# Schematic.net
KiCad netlist of a schematic drawn in Altium Designer
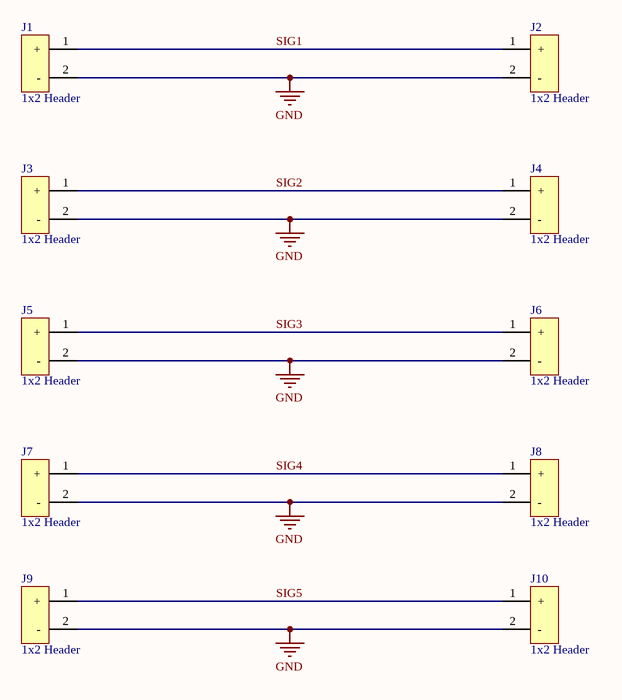
[diagram p0: Schematic.SchDoc]

(export (version "E")
  (design (tool "Eeschema 10.0.6"))
  (components
    (comp (ref "J1")
      (value "1x2 Header")
      (footprint "HDR1X2")
      (description "Headers & Wire Housings 2 PIN F/LK HEADER")
      (fields (field (name "MANUFACTURER") "Molex") (field (name "MANUFACTURER PART NUMBER") "22-29-2021"))
      (libsource (lib "") (part "22-29-2021_1"))
    )
    (comp (ref "J2")
      (value "1x2 Header")
      (footprint "HDR1X2")
      (description "Headers & Wire Housings 2 PIN F/LK HEADER")
      (fields (field (name "MANUFACTURER") "Molex") (field (name "MANUFACTURER PART NUMBER") "22-29-2021"))
      (libsource (lib "Schlib") (part "22-29-2021"))
    )
    (comp (ref "J3")
      (value "1x2 Header")
      (footprint "HDR1X2")
      (description "Headers & Wire Housings 2 PIN F/LK HEADER")
      (fields (field (name "MANUFACTURER") "Molex") (field (name "MANUFACTURER PART NUMBER") "22-29-2021"))
      (libsource (lib "") (part "22-29-2021_1"))
    )
    (comp (ref "J4")
      (value "1x2 Header")
      (footprint "HDR1X2")
      (description "Headers & Wire Housings 2 PIN F/LK HEADER")
      (fields (field (name "MANUFACTURER") "Molex") (field (name "MANUFACTURER PART NUMBER") "22-29-2021"))
      (libsource (lib "Schlib") (part "22-29-2021"))
    )
    (comp (ref "J5")
      (value "1x2 Header")
      (footprint "HDR1X2")
      (description "Headers & Wire Housings 2 PIN F/LK HEADER")
      (fields (field (name "MANUFACTURER") "Molex") (field (name "MANUFACTURER PART NUMBER") "22-29-2021"))
      (libsource (lib "") (part "22-29-2021_1"))
    )
    (comp (ref "J6")
      (value "1x2 Header")
      (footprint "HDR1X2")
      (description "Headers & Wire Housings 2 PIN F/LK HEADER")
      (fields (field (name "MANUFACTURER") "Molex") (field (name "MANUFACTURER PART NUMBER") "22-29-2021"))
      (libsource (lib "Schlib") (part "22-29-2021"))
    )
    (comp (ref "J7")
      (value "1x2 Header")
      (footprint "HDR1X2")
      (description "Headers & Wire Housings 2 PIN F/LK HEADER")
      (fields (field (name "MANUFACTURER") "Molex") (field (name "MANUFACTURER PART NUMBER") "22-29-2021"))
      (libsource (lib "") (part "22-29-2021_1"))
    )
    (comp (ref "J8")
      (value "1x2 Header")
      (footprint "HDR1X2")
      (description "Headers & Wire Housings 2 PIN F/LK HEADER")
      (fields (field (name "MANUFACTURER") "Molex") (field (name "MANUFACTURER PART NUMBER") "22-29-2021"))
      (libsource (lib "Schlib") (part "22-29-2021"))
    )
    (comp (ref "J9")
      (value "1x2 Header")
      (footprint "HDR1X2")
      (description "Headers & Wire Housings 2 PIN F/LK HEADER")
      (fields (field (name "MANUFACTURER") "Molex") (field (name "MANUFACTURER PART NUMBER") "22-29-2021"))
      (libsource (lib "") (part "22-29-2021_1"))
    )
    (comp (ref "J10")
      (value "1x2 Header")
      (footprint "HDR1X2")
      (description "Headers & Wire Housings 2 PIN F/LK HEADER")
      (fields (field (name "MANUFACTURER") "Molex") (field (name "MANUFACTURER PART NUMBER") "22-29-2021"))
      (libsource (lib "Schlib") (part "22-29-2021"))
    )
  )
  (nets
    (net (code "1") (name "/SIG1") (class "Default")
      (node (ref "J1") (pin "1") (pinfunction "+_1") (pintype "passive"))
      (node (ref "J2") (pin "1") (pinfunction "+_1") (pintype "passive"))
    )
    (net (code "2") (name "/SIG2") (class "Default")
      (node (ref "J3") (pin "1") (pinfunction "+_1") (pintype "passive"))
      (node (ref "J4") (pin "1") (pinfunction "+_1") (pintype "passive"))
    )
    (net (code "3") (name "/SIG3") (class "Default")
      (node (ref "J5") (pin "1") (pinfunction "+_1") (pintype "passive"))
      (node (ref "J6") (pin "1") (pinfunction "+_1") (pintype "passive"))
    )
    (net (code "4") (name "/SIG4") (class "Default")
      (node (ref "J7") (pin "1") (pinfunction "+_1") (pintype "passive"))
      (node (ref "J8") (pin "1") (pinfunction "+_1") (pintype "passive"))
    )
    (net (code "5") (name "/SIG5") (class "Default")
      (node (ref "J10") (pin "1") (pinfunction "+_1") (pintype "passive"))
      (node (ref "J9") (pin "1") (pinfunction "+_1") (pintype "passive"))
    )
    (net (code "6") (name "GND") (class "Default")
      (node (ref "J1") (pin "2") (pinfunction "-_2") (pintype "passive"))
      (node (ref "J10") (pin "2") (pinfunction "-_2") (pintype "passive"))
      (node (ref "J2") (pin "2") (pinfunction "-_2") (pintype "passive"))
      (node (ref "J3") (pin "2") (pinfunction "-_2") (pintype "passive"))
      (node (ref "J4") (pin "2") (pinfunction "-_2") (pintype "passive"))
      (node (ref "J5") (pin "2") (pinfunction "-_2") (pintype "passive"))
      (node (ref "J6") (pin "2") (pinfunction "-_2") (pintype "passive"))
      (node (ref "J7") (pin "2") (pinfunction "-_2") (pintype "passive"))
      (node (ref "J8") (pin "2") (pinfunction "-_2") (pintype "passive"))
      (node (ref "J9") (pin "2") (pinfunction "-_2") (pintype "passive"))
    )
  )
)
